# sensbase.net
KiCad netlist of a schematic drawn in EAGLE
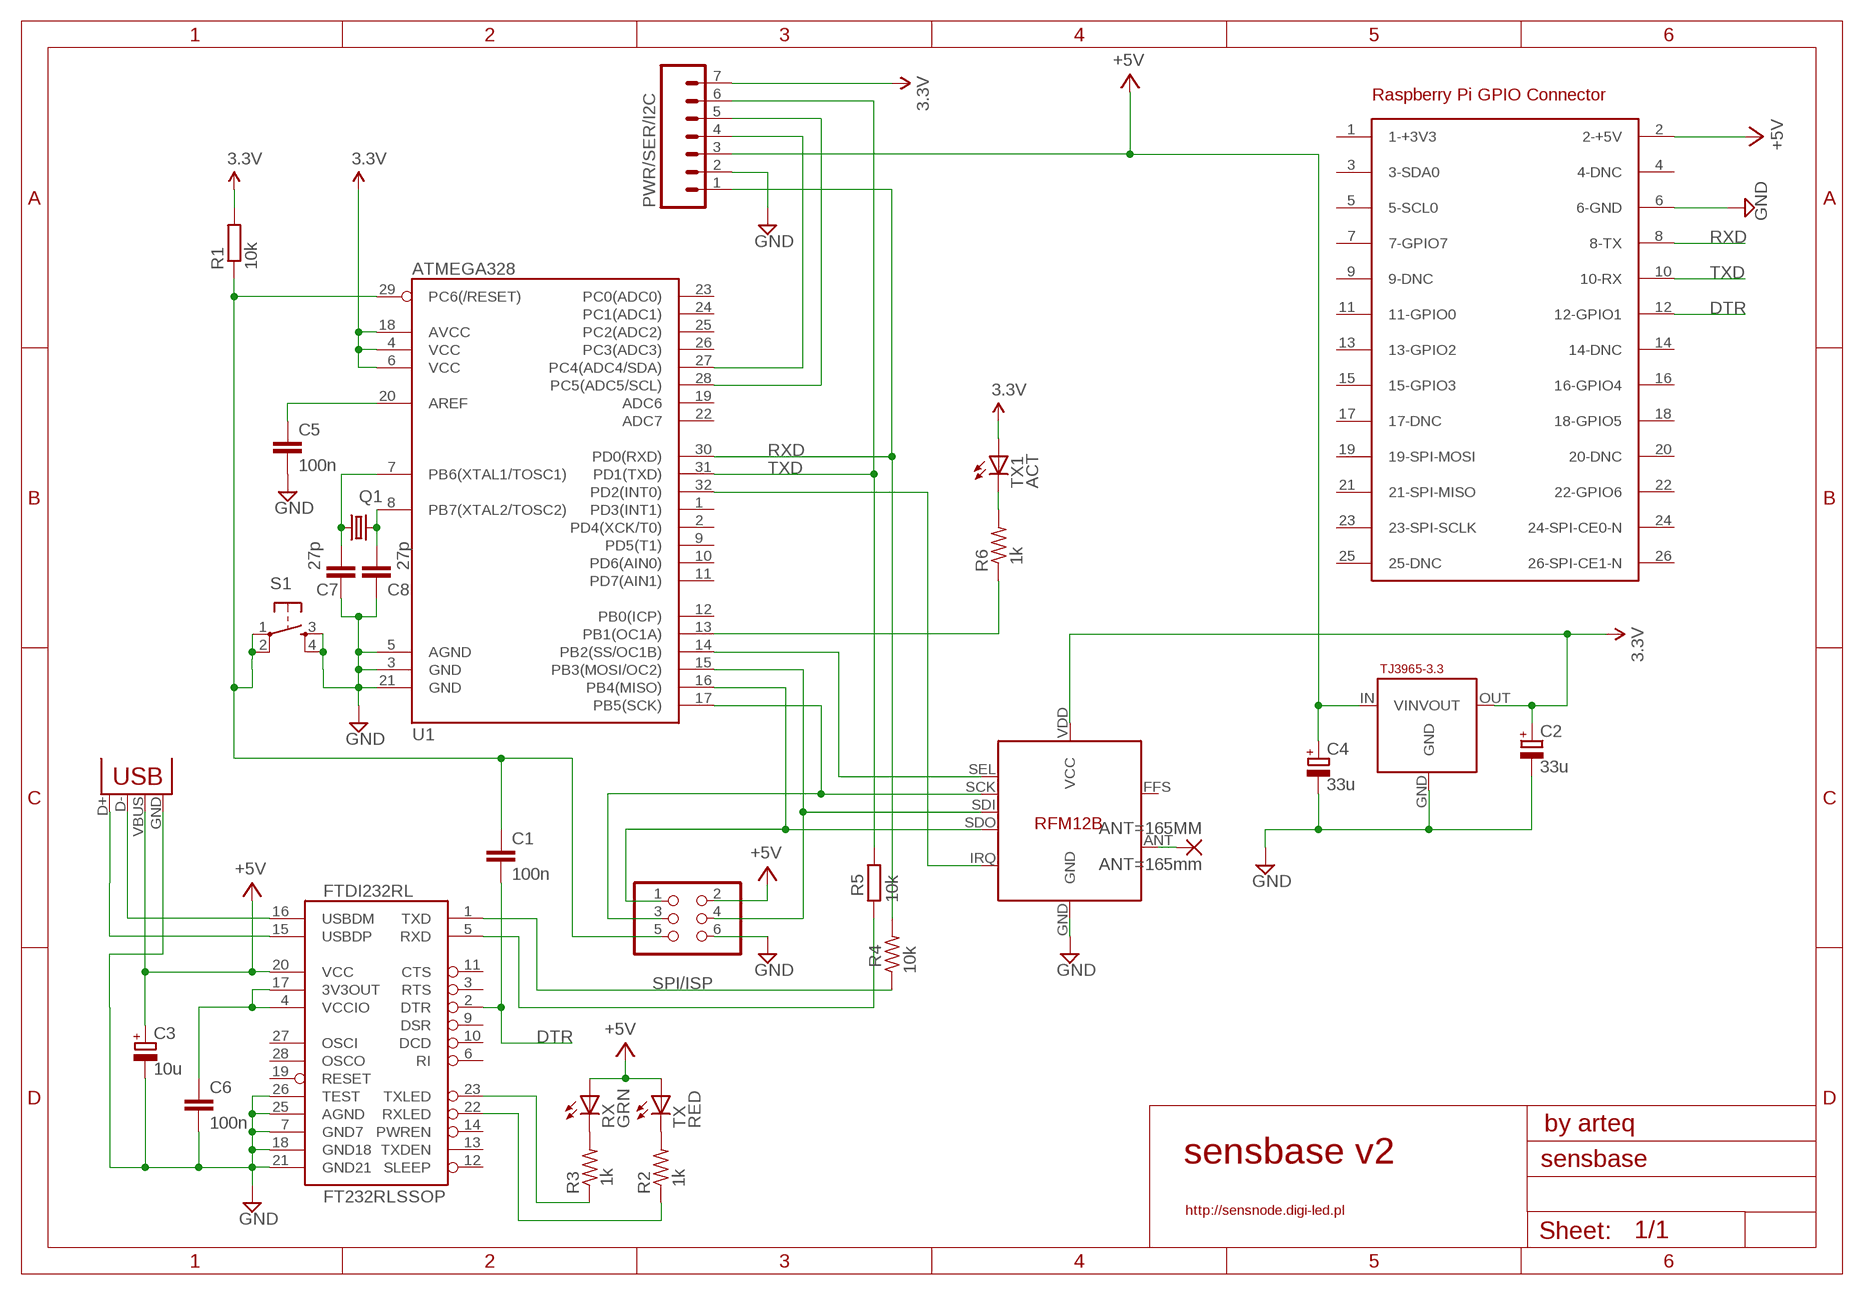
[diagram p0: schematic, sheet 1]

(export (version "E")
  (design (tool "Eeschema 10.0.6"))
  (components
    (comp (ref "3.3")
      (value "TJ3965-3.3")
      (footprint "eagle-import:SOT223")
      (libsource (lib "eagle-import") (part "TJ3965-3.3"))
    )
    (comp (ref "ANT=165MM")
      (value "ANT=165mm")
      (footprint "eagle-import:1,6_0,9")
      (libsource (lib "eagle-import") (part "1,6/0,9"))
    )
    (comp (ref "C1")
      (value "100n")
      (footprint "eagle-import:C0805")
      (libsource (lib "eagle-import") (part "C-EUC0805"))
    )
    (comp (ref "C2")
      (value "33u")
      (footprint "eagle-import:SMC_B")
      (libsource (lib "eagle-import") (part "CPOL-EUSMCB"))
    )
    (comp (ref "C3")
      (value "10u")
      (footprint "eagle-import:SMC_A")
      (libsource (lib "eagle-import") (part "CPOL-EUSMCA"))
    )
    (comp (ref "C4")
      (value "33u")
      (footprint "eagle-import:SMC_B")
      (libsource (lib "eagle-import") (part "CPOL-EUSMCB"))
    )
    (comp (ref "C5")
      (value "100n")
      (footprint "eagle-import:C0805")
      (libsource (lib "eagle-import") (part "C-EUC0805"))
    )
    (comp (ref "C6")
      (value "100n")
      (footprint "eagle-import:C0805")
      (libsource (lib "eagle-import") (part "C-EUC0805"))
    )
    (comp (ref "C7")
      (value "27p")
      (footprint "eagle-import:C0805")
      (libsource (lib "eagle-import") (part "C-EUC0805"))
    )
    (comp (ref "C8")
      (value "27p")
      (footprint "eagle-import:C0805")
      (libsource (lib "eagle-import") (part "C-EUC0805"))
    )
    (comp (ref "FTDI232RL")
      (value "FT232RLSSOP")
      (footprint "eagle-import:SSOP28DB")
      (libsource (lib "eagle-import") (part "FT232RLSSOP"))
    )
    (comp (ref "PWR/SER/I2C")
      (value "PSI")
      (footprint "eagle-import:1X07")
      (libsource (lib "eagle-import") (part "M07"))
    )
    (comp (ref "Q1")
      (value "CRYSTALHC49UP")
      (footprint "eagle-import:HC49UP")
      (libsource (lib "eagle-import") (part "CRYSTALHC49UP"))
    )
    (comp (ref "R1")
      (value "10k")
      (footprint "eagle-import:R0805")
      (libsource (lib "eagle-import") (part "R-EU_R0805"))
    )
    (comp (ref "R2")
      (value "1k")
      (footprint "eagle-import:R0805@1")
      (libsource (lib "eagle-import") (part "R-US_R0805"))
    )
    (comp (ref "R3")
      (value "1k")
      (footprint "eagle-import:R0805@1")
      (libsource (lib "eagle-import") (part "R-US_R0805"))
    )
    (comp (ref "R4")
      (value "10k")
      (footprint "eagle-import:R0805@1")
      (libsource (lib "eagle-import") (part "R-US_R0805"))
    )
    (comp (ref "R5")
      (value "10k")
      (footprint "eagle-import:R0805")
      (libsource (lib "eagle-import") (part "R-EU_R0805"))
    )
    (comp (ref "R6")
      (value "1k")
      (footprint "eagle-import:R0805@1")
      (libsource (lib "eagle-import") (part "R-US_R0805"))
    )
    (comp (ref "RF433")
      (value "RFM12B")
      (footprint "eagle-import:RFM12B")
      (libsource (lib "eagle-import") (part "RFM12B"))
    )
    (comp (ref "RX")
      (value "GRN")
      (footprint "eagle-import:CHIP-LED0805")
      (libsource (lib "eagle-import") (part "LEDCHIP-LED0805"))
    )
    (comp (ref "S1")
      (value "TAC_SWITCHSMD")
      (footprint "eagle-import:TACTILE_SWITCH_SMD")
      (libsource (lib "eagle-import") (part "TAC_SWITCHSMD"))
    )
    (comp (ref "SV7")
      (value "SPI/ISP")
      (footprint "eagle-import:2X03")
      (libsource (lib "eagle-import") (part "PINHD-2X3"))
    )
    (comp (ref "TX")
      (value "RED")
      (footprint "eagle-import:CHIP-LED0805")
      (libsource (lib "eagle-import") (part "LEDCHIP-LED0805"))
    )
    (comp (ref "TX1")
      (value "ACT")
      (footprint "eagle-import:CHIP-LED0805")
      (libsource (lib "eagle-import") (part "LEDCHIP-LED0805"))
    )
    (comp (ref "U$2")
      (value "RASPBERRY-PI")
      (footprint "eagle-import:RASPBERRY-PI")
      (libsource (lib "eagle-import") (part "RASPBERRY-PI"))
    )
    (comp (ref "U1")
      (value "ATMEGA328")
      (footprint "eagle-import:TQFP32-08")
      (libsource (lib "eagle-import") (part "ATMEGA168"))
    )
    (comp (ref "X1")
      (value "USBSMD")
      (footprint "eagle-import:USB-MINIB")
      (libsource (lib "eagle-import") (part "USBSMD"))
    )
  )
  (nets
    (net (code "1") (name "+5V") (class "Default")
      (node (ref "3.3") (pin "IN") (pinfunction "VIN_IN") (pintype "input"))
      (node (ref "C3") (pin "+") (pinfunction "+_+") (pintype "passive"))
      (node (ref "C4") (pin "+") (pinfunction "+_+") (pintype "passive"))
      (node (ref "FTDI232RL") (pin "20") (pinfunction "VCC_20") (pintype "power_in"))
      (node (ref "PWR/SER/I2C") (pin "3") (pinfunction "3_3") (pintype "passive"))
      (node (ref "RX") (pin "A") (pinfunction "A_A") (pintype "passive"))
      (node (ref "SV7") (pin "2") (pinfunction "2_2") (pintype "passive"))
      (node (ref "TX") (pin "A") (pinfunction "A_A") (pintype "passive"))
      (node (ref "U$2") (pin "2") (pinfunction "2-+5V_2") (pintype "bidirectional"))
      (node (ref "X1") (pin "VBUS") (pinfunction "VBUS_VBUS") (pintype "bidirectional"))
    )
    (net (code "2") (name "/DTR") (class "Default")
      (node (ref "C1") (pin "2") (pinfunction "2_2") (pintype "passive"))
      (node (ref "FTDI232RL") (pin "2") (pinfunction "DTR_2") (pintype "output"))
      (node (ref "U$2") (pin "12") (pinfunction "12-GPIO1_12") (pintype "bidirectional"))
    )
    (net (code "3") (name "/RXD") (class "Default")
      (node (ref "PWR/SER/I2C") (pin "1") (pinfunction "1_1") (pintype "passive"))
      (node (ref "R4") (pin "2") (pinfunction "2_2") (pintype "passive"))
      (node (ref "U$2") (pin "8") (pinfunction "8-TX_8") (pintype "bidirectional"))
      (node (ref "U1") (pin "30") (pinfunction "PD0(RXD)_30") (pintype "bidirectional"))
    )
    (net (code "4") (name "/TXD") (class "Default")
      (node (ref "PWR/SER/I2C") (pin "6") (pinfunction "6_6") (pintype "passive"))
      (node (ref "R5") (pin "2") (pinfunction "2_2") (pintype "passive"))
      (node (ref "U$2") (pin "10") (pinfunction "10-RX_10") (pintype "bidirectional"))
      (node (ref "U1") (pin "31") (pinfunction "PD1(TXD)_31") (pintype "bidirectional"))
    )
    (net (code "5") (name "3.3V") (class "Default")
      (node (ref "3.3") (pin "OUT") (pinfunction "VOUT_OUT") (pintype "output"))
      (node (ref "C2") (pin "+") (pinfunction "+_+") (pintype "passive"))
      (node (ref "PWR/SER/I2C") (pin "7") (pinfunction "7_7") (pintype "passive"))
      (node (ref "R1") (pin "2") (pinfunction "2_2") (pintype "passive"))
      (node (ref "RF433") (pin "VDD") (pinfunction "VCC_VDD") (pintype "power_in"))
      (node (ref "TX1") (pin "A") (pinfunction "A_A") (pintype "passive"))
      (node (ref "U1") (pin "18") (pinfunction "AVCC_18") (pintype "bidirectional"))
      (node (ref "U1") (pin "4") (pinfunction "VCC_4") (pintype "bidirectional"))
      (node (ref "U1") (pin "6") (pinfunction "VCC_6") (pintype "bidirectional"))
    )
    (net (code "6") (name "GND") (class "Default")
      (node (ref "3.3") (pin "GND") (pinfunction "GND_GND") (pintype "power_in"))
      (node (ref "C2") (pin "-") (pinfunction "-_-") (pintype "passive"))
      (node (ref "C3") (pin "-") (pinfunction "-_-") (pintype "passive"))
      (node (ref "C4") (pin "-") (pinfunction "-_-") (pintype "passive"))
      (node (ref "C5") (pin "2") (pinfunction "2_2") (pintype "passive"))
      (node (ref "C6") (pin "2") (pinfunction "2_2") (pintype "passive"))
      (node (ref "C7") (pin "2") (pinfunction "2_2") (pintype "passive"))
      (node (ref "C8") (pin "2") (pinfunction "2_2") (pintype "passive"))
      (node (ref "FTDI232RL") (pin "18") (pinfunction "GND18_18") (pintype "power_in"))
      (node (ref "FTDI232RL") (pin "21") (pinfunction "GND21_21") (pintype "power_in"))
      (node (ref "FTDI232RL") (pin "25") (pinfunction "AGND_25") (pintype "power_in"))
      (node (ref "FTDI232RL") (pin "26") (pinfunction "TEST_26") (pintype "input"))
      (node (ref "FTDI232RL") (pin "7") (pinfunction "GND7_7") (pintype "power_in"))
      (node (ref "PWR/SER/I2C") (pin "2") (pinfunction "2_2") (pintype "passive"))
      (node (ref "RF433") (pin "GND") (pinfunction "GND_GND") (pintype "power_in"))
      (node (ref "S1") (pin "3") (pinfunction "3_3") (pintype "passive"))
      (node (ref "S1") (pin "4") (pinfunction "4_4") (pintype "passive"))
      (node (ref "SV7") (pin "6") (pinfunction "6_6") (pintype "passive"))
      (node (ref "U$2") (pin "6") (pinfunction "6-GND_6") (pintype "bidirectional"))
      (node (ref "U1") (pin "21") (pinfunction "GND_21") (pintype "bidirectional"))
      (node (ref "U1") (pin "3") (pinfunction "GND_3") (pintype "bidirectional"))
      (node (ref "U1") (pin "5") (pinfunction "AGND_5") (pintype "bidirectional"))
      (node (ref "X1") (pin "GND") (pinfunction "GND_GND") (pintype "bidirectional"))
    )
    (net (code "7") (name "Net-(ANT=165MM-P)") (class "Default")
      (node (ref "ANT=165MM") (pin "1") (pinfunction "P_1") (pintype "passive"))
      (node (ref "RF433") (pin "ANT") (pinfunction "ANT_ANT") (pintype "passive"))
    )
    (net (code "8") (name "Net-(FTDI232RL-3V3OUT)") (class "Default")
      (node (ref "C6") (pin "1") (pinfunction "1_1") (pintype "passive"))
      (node (ref "FTDI232RL") (pin "17") (pinfunction "3V3OUT_17") (pintype "output"))
      (node (ref "FTDI232RL") (pin "4") (pinfunction "VCCIO_4") (pintype "power_in"))
    )
    (net (code "9") (name "Net-(FTDI232RL-RXD)") (class "Default")
      (node (ref "FTDI232RL") (pin "5") (pinfunction "RXD_5") (pintype "input"))
      (node (ref "R5") (pin "1") (pinfunction "1_1") (pintype "passive"))
    )
    (net (code "10") (name "Net-(FTDI232RL-RXLED)") (class "Default")
      (node (ref "FTDI232RL") (pin "22") (pinfunction "RXLED_22") (pintype "input"))
      (node (ref "R2") (pin "1") (pinfunction "1_1") (pintype "passive"))
    )
    (net (code "11") (name "Net-(FTDI232RL-TXD)") (class "Default")
      (node (ref "FTDI232RL") (pin "1") (pinfunction "TXD_1") (pintype "output"))
      (node (ref "R4") (pin "1") (pinfunction "1_1") (pintype "passive"))
    )
    (net (code "12") (name "Net-(FTDI232RL-TXLED)") (class "Default")
      (node (ref "FTDI232RL") (pin "23") (pinfunction "TXLED_23") (pintype "input"))
      (node (ref "R3") (pin "1") (pinfunction "1_1") (pintype "passive"))
    )
    (net (code "13") (name "Net-(FTDI232RL-USBDM)") (class "Default")
      (node (ref "FTDI232RL") (pin "16") (pinfunction "USBDM_16") (pintype "bidirectional"))
      (node (ref "X1") (pin "D-") (pinfunction "D-_D-") (pintype "bidirectional"))
    )
    (net (code "14") (name "Net-(FTDI232RL-USBDP)") (class "Default")
      (node (ref "FTDI232RL") (pin "15") (pinfunction "USBDP_15") (pintype "bidirectional"))
      (node (ref "X1") (pin "D+") (pinfunction "D+_D+") (pintype "bidirectional"))
    )
    (net (code "15") (name "Net-(R2-Pad2)") (class "Default")
      (node (ref "R2") (pin "2") (pinfunction "2_2") (pintype "passive"))
      (node (ref "TX") (pin "C") (pinfunction "C_C") (pintype "passive"))
    )
    (net (code "16") (name "Net-(R3-Pad2)") (class "Default")
      (node (ref "R3") (pin "2") (pinfunction "2_2") (pintype "passive"))
      (node (ref "RX") (pin "C") (pinfunction "C_C") (pintype "passive"))
    )
    (net (code "17") (name "Net-(R6-Pad2)") (class "Default")
      (node (ref "R6") (pin "2") (pinfunction "2_2") (pintype "passive"))
      (node (ref "TX1") (pin "C") (pinfunction "C_C") (pintype "passive"))
    )
    (net (code "18") (name "Net-(U1-AREF)") (class "Default")
      (node (ref "C5") (pin "1") (pinfunction "1_1") (pintype "passive"))
      (node (ref "U1") (pin "20") (pinfunction "AREF_20") (pintype "bidirectional"))
    )
    (net (code "19") (name "Net-(U1-PB1(OC1A))") (class "Default")
      (node (ref "R6") (pin "1") (pinfunction "1_1") (pintype "passive"))
      (node (ref "U1") (pin "13") (pinfunction "PB1(OC1A)_13") (pintype "bidirectional"))
    )
    (net (code "20") (name "Net-(U1-PB2(SS{slash}OC1B))") (class "Default")
      (node (ref "RF433") (pin "SEL") (pinfunction "SEL_SEL") (pintype "input"))
      (node (ref "U1") (pin "14") (pinfunction "PB2(SS/OC1B)_14") (pintype "bidirectional"))
    )
    (net (code "21") (name "Net-(U1-PB3(MOSI{slash}OC2))") (class "Default")
      (node (ref "RF433") (pin "SDI") (pinfunction "SDI_SDI") (pintype "input"))
      (node (ref "SV7") (pin "4") (pinfunction "4_4") (pintype "passive"))
      (node (ref "U1") (pin "15") (pinfunction "PB3(MOSI/OC2)_15") (pintype "bidirectional"))
    )
    (net (code "22") (name "Net-(U1-PB4(MISO))") (class "Default")
      (node (ref "RF433") (pin "SDO") (pinfunction "SDO_SDO") (pintype "output"))
      (node (ref "SV7") (pin "1") (pinfunction "1_1") (pintype "passive"))
      (node (ref "U1") (pin "16") (pinfunction "PB4(MISO)_16") (pintype "bidirectional"))
    )
    (net (code "23") (name "Net-(U1-PB5(SCK))") (class "Default")
      (node (ref "RF433") (pin "SCK") (pinfunction "SCK_SCK") (pintype "input"))
      (node (ref "SV7") (pin "3") (pinfunction "3_3") (pintype "passive"))
      (node (ref "U1") (pin "17") (pinfunction "PB5(SCK)_17") (pintype "bidirectional"))
    )
    (net (code "24") (name "Net-(U1-PB6(XTAL1{slash}TOSC1))") (class "Default")
      (node (ref "C7") (pin "1") (pinfunction "1_1") (pintype "passive"))
      (node (ref "Q1") (pin "1") (pinfunction "1_1") (pintype "passive"))
      (node (ref "U1") (pin "7") (pinfunction "PB6(XTAL1/TOSC1)_7") (pintype "bidirectional"))
    )
    (net (code "25") (name "Net-(U1-PB7(XTAL2{slash}TOSC2))") (class "Default")
      (node (ref "C8") (pin "1") (pinfunction "1_1") (pintype "passive"))
      (node (ref "Q1") (pin "2") (pinfunction "2_2") (pintype "passive"))
      (node (ref "U1") (pin "8") (pinfunction "PB7(XTAL2/TOSC2)_8") (pintype "bidirectional"))
    )
    (net (code "26") (name "Net-(U1-PC4(ADC4{slash}SDA))") (class "Default")
      (node (ref "PWR/SER/I2C") (pin "4") (pinfunction "4_4") (pintype "passive"))
      (node (ref "U1") (pin "27") (pinfunction "PC4(ADC4/SDA)_27") (pintype "bidirectional"))
    )
    (net (code "27") (name "Net-(U1-PC5(ADC5{slash}SCL))") (class "Default")
      (node (ref "PWR/SER/I2C") (pin "5") (pinfunction "5_5") (pintype "passive"))
      (node (ref "U1") (pin "28") (pinfunction "PC5(ADC5/SCL)_28") (pintype "bidirectional"))
    )
    (net (code "28") (name "Net-(U1-PC6({slash}RESET))") (class "Default")
      (node (ref "C1") (pin "1") (pinfunction "1_1") (pintype "passive"))
      (node (ref "R1") (pin "1") (pinfunction "1_1") (pintype "passive"))
      (node (ref "S1") (pin "1") (pinfunction "1_1") (pintype "passive"))
      (node (ref "S1") (pin "2") (pinfunction "2_2") (pintype "passive"))
      (node (ref "SV7") (pin "5") (pinfunction "5_5") (pintype "passive"))
      (node (ref "U1") (pin "29") (pinfunction "PC6(/RESET)_29") (pintype "bidirectional"))
    )
    (net (code "29") (name "Net-(U1-PD2(INT0))") (class "Default")
      (node (ref "RF433") (pin "IRQ") (pinfunction "IRQ_IRQ") (pintype "open_collector"))
      (node (ref "U1") (pin "32") (pinfunction "PD2(INT0)_32") (pintype "bidirectional"))
    )
    (net (code "30") (name "unconnected-(FTDI232RL-CTS-Pad11)") (class "Default")
      (node (ref "FTDI232RL") (pin "11") (pinfunction "CTS_11") (pintype "input"))
    )
    (net (code "31") (name "unconnected-(FTDI232RL-DCD-Pad10)") (class "Default")
      (node (ref "FTDI232RL") (pin "10") (pinfunction "DCD_10") (pintype "input"))
    )
    (net (code "32") (name "unconnected-(FTDI232RL-DSR-Pad9)") (class "Default")
      (node (ref "FTDI232RL") (pin "9") (pinfunction "DSR_9") (pintype "input"))
    )
    (net (code "33") (name "unconnected-(FTDI232RL-OSCI-Pad27)") (class "Default")
      (node (ref "FTDI232RL") (pin "27") (pinfunction "OSCI_27") (pintype "input"))
    )
    (net (code "34") (name "unconnected-(FTDI232RL-OSCO-Pad28)") (class "Default")
      (node (ref "FTDI232RL") (pin "28") (pinfunction "OSCO_28") (pintype "output"))
    )
    (net (code "35") (name "unconnected-(FTDI232RL-PWREN-Pad14)") (class "Default")
      (node (ref "FTDI232RL") (pin "14") (pinfunction "PWREN_14") (pintype "input"))
    )
    (net (code "36") (name "unconnected-(FTDI232RL-RESET-Pad19)") (class "Default")
      (node (ref "FTDI232RL") (pin "19") (pinfunction "RESET_19") (pintype "input"))
    )
    (net (code "37") (name "unconnected-(FTDI232RL-RI-Pad6)") (class "Default")
      (node (ref "FTDI232RL") (pin "6") (pinfunction "RI_6") (pintype "input"))
    )
    (net (code "38") (name "unconnected-(FTDI232RL-RTS-Pad3)") (class "Default")
      (node (ref "FTDI232RL") (pin "3") (pinfunction "RTS_3") (pintype "output"))
    )
    (net (code "39") (name "unconnected-(FTDI232RL-SLEEP-Pad12)") (class "Default")
      (node (ref "FTDI232RL") (pin "12") (pinfunction "SLEEP_12") (pintype "input"))
    )
    (net (code "40") (name "unconnected-(FTDI232RL-TXDEN-Pad13)") (class "Default")
      (node (ref "FTDI232RL") (pin "13") (pinfunction "TXDEN_13") (pintype "input"))
    )
    (net (code "41") (name "unconnected-(RF433-PadFFS)") (class "Default")
      (node (ref "RF433") (pin "FFS") (pinfunction "FFS_FFS") (pintype "bidirectional"))
    )
    (net (code "42") (name "unconnected-(U$2-1-+3V3-Pad1)") (class "Default")
      (node (ref "U$2") (pin "1") (pinfunction "1-+3V3_1") (pintype "bidirectional"))
    )
    (net (code "43") (name "unconnected-(U$2-3-SDA0-Pad3)") (class "Default")
      (node (ref "U$2") (pin "3") (pinfunction "3-SDA0_3") (pintype "bidirectional"))
    )
    (net (code "44") (name "unconnected-(U$2-4-DNC-Pad4)") (class "Default")
      (node (ref "U$2") (pin "4") (pinfunction "4-DNC_4") (pintype "bidirectional"))
    )
    (net (code "45") (name "unconnected-(U$2-5-SCL0-Pad5)") (class "Default")
      (node (ref "U$2") (pin "5") (pinfunction "5-SCL0_5") (pintype "bidirectional"))
    )
    (net (code "46") (name "unconnected-(U$2-7-GPIO7-Pad7)") (class "Default")
      (node (ref "U$2") (pin "7") (pinfunction "7-GPIO7_7") (pintype "bidirectional"))
    )
    (net (code "47") (name "unconnected-(U$2-9-DNC-Pad9)") (class "Default")
      (node (ref "U$2") (pin "9") (pinfunction "9-DNC_9") (pintype "bidirectional"))
    )
    (net (code "48") (name "unconnected-(U$2-11-GPIO0-Pad11)") (class "Default")
      (node (ref "U$2") (pin "11") (pinfunction "11-GPIO0_11") (pintype "bidirectional"))
    )
    (net (code "49") (name "unconnected-(U$2-13-GPIO2-Pad13)") (class "Default")
      (node (ref "U$2") (pin "13") (pinfunction "13-GPIO2_13") (pintype "bidirectional"))
    )
    (net (code "50") (name "unconnected-(U$2-14-DNC-Pad14)") (class "Default")
      (node (ref "U$2") (pin "14") (pinfunction "14-DNC_14") (pintype "bidirectional"))
    )
    (net (code "51") (name "unconnected-(U$2-15-GPIO3-Pad15)") (class "Default")
      (node (ref "U$2") (pin "15") (pinfunction "15-GPIO3_15") (pintype "bidirectional"))
    )
    (net (code "52") (name "unconnected-(U$2-16-GPIO4-Pad16)") (class "Default")
      (node (ref "U$2") (pin "16") (pinfunction "16-GPIO4_16") (pintype "bidirectional"))
    )
    (net (code "53") (name "unconnected-(U$2-17-DNC-Pad17)") (class "Default")
      (node (ref "U$2") (pin "17") (pinfunction "17-DNC_17") (pintype "bidirectional"))
    )
    (net (code "54") (name "unconnected-(U$2-18-GPIO5-Pad18)") (class "Default")
      (node (ref "U$2") (pin "18") (pinfunction "18-GPIO5_18") (pintype "bidirectional"))
    )
    (net (code "55") (name "unconnected-(U$2-19-SPI-MOSI-Pad19)") (class "Default")
      (node (ref "U$2") (pin "19") (pinfunction "19-SPI-MOSI_19") (pintype "bidirectional"))
    )
    (net (code "56") (name "unconnected-(U$2-20-DNC-Pad20)") (class "Default")
      (node (ref "U$2") (pin "20") (pinfunction "20-DNC_20") (pintype "bidirectional"))
    )
    (net (code "57") (name "unconnected-(U$2-21-SPI-MISO-Pad21)") (class "Default")
      (node (ref "U$2") (pin "21") (pinfunction "21-SPI-MISO_21") (pintype "bidirectional"))
    )
    (net (code "58") (name "unconnected-(U$2-22-GPIO6-Pad22)") (class "Default")
      (node (ref "U$2") (pin "22") (pinfunction "22-GPIO6_22") (pintype "bidirectional"))
    )
    (net (code "59") (name "unconnected-(U$2-23-SPI-SCLK-Pad23)") (class "Default")
      (node (ref "U$2") (pin "23") (pinfunction "23-SPI-SCLK_23") (pintype "bidirectional"))
    )
    (net (code "60") (name "unconnected-(U$2-24-SPI-CE0-N-Pad24)") (class "Default")
      (node (ref "U$2") (pin "24") (pinfunction "24-SPI-CE0-N_24") (pintype "bidirectional"))
    )
    (net (code "61") (name "unconnected-(U$2-25-DNC-Pad25)") (class "Default")
      (node (ref "U$2") (pin "25") (pinfunction "25-DNC_25") (pintype "bidirectional"))
    )
    (net (code "62") (name "unconnected-(U$2-26-SPI-CE1-N-Pad26)") (class "Default")
      (node (ref "U$2") (pin "26") (pinfunction "26-SPI-CE1-N_26") (pintype "bidirectional"))
    )
    (net (code "63") (name "unconnected-(U1-ADC6-Pad19)") (class "Default")
      (node (ref "U1") (pin "19") (pinfunction "ADC6_19") (pintype "bidirectional"))
    )
    (net (code "64") (name "unconnected-(U1-ADC7-Pad22)") (class "Default")
      (node (ref "U1") (pin "22") (pinfunction "ADC7_22") (pintype "bidirectional"))
    )
    (net (code "65") (name "unconnected-(U1-PB0(ICP)-Pad12)") (class "Default")
      (node (ref "U1") (pin "12") (pinfunction "PB0(ICP)_12") (pintype "bidirectional"))
    )
    (net (code "66") (name "unconnected-(U1-PC0(ADC0)-Pad23)") (class "Default")
      (node (ref "U1") (pin "23") (pinfunction "PC0(ADC0)_23") (pintype "bidirectional"))
    )
    (net (code "67") (name "unconnected-(U1-PC1(ADC1)-Pad24)") (class "Default")
      (node (ref "U1") (pin "24") (pinfunction "PC1(ADC1)_24") (pintype "bidirectional"))
    )
    (net (code "68") (name "unconnected-(U1-PC2(ADC2)-Pad25)") (class "Default")
      (node (ref "U1") (pin "25") (pinfunction "PC2(ADC2)_25") (pintype "bidirectional"))
    )
    (net (code "69") (name "unconnected-(U1-PC3(ADC3)-Pad26)") (class "Default")
      (node (ref "U1") (pin "26") (pinfunction "PC3(ADC3)_26") (pintype "bidirectional"))
    )
    (net (code "70") (name "unconnected-(U1-PD3(INT1)-Pad1)") (class "Default")
      (node (ref "U1") (pin "1") (pinfunction "PD3(INT1)_1") (pintype "bidirectional"))
    )
    (net (code "71") (name "unconnected-(U1-PD4(XCK{slash}T0)-Pad2)") (class "Default")
      (node (ref "U1") (pin "2") (pinfunction "PD4(XCK/T0)_2") (pintype "bidirectional"))
    )
    (net (code "72") (name "unconnected-(U1-PD5(T1)-Pad9)") (class "Default")
      (node (ref "U1") (pin "9") (pinfunction "PD5(T1)_9") (pintype "bidirectional"))
    )
    (net (code "73") (name "unconnected-(U1-PD6(AIN0)-Pad10)") (class "Default")
      (node (ref "U1") (pin "10") (pinfunction "PD6(AIN0)_10") (pintype "bidirectional"))
    )
    (net (code "74") (name "unconnected-(U1-PD7(AIN1)-Pad11)") (class "Default")
      (node (ref "U1") (pin "11") (pinfunction "PD7(AIN1)_11") (pintype "bidirectional"))
    )
  )
)
